# RS-485.net
KiCad netlist of a schematic drawn in Altium Designer
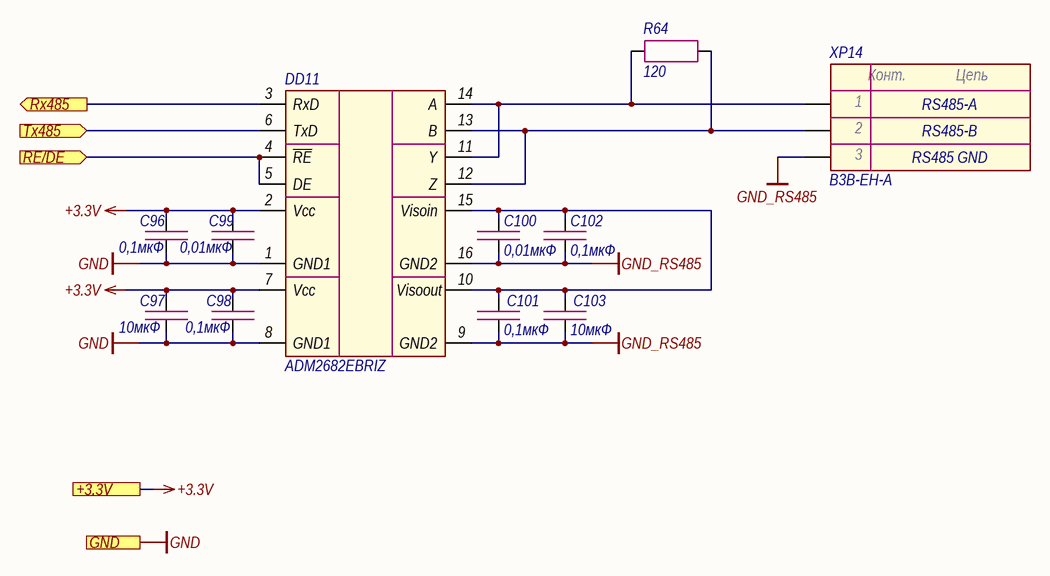
[diagram p0: RS-485.SchDoc]

(export (version "E")
  (design (tool "Eeschema 10.0.6"))
  (components
    (comp (ref "C96")
      (value "0,1мкФ")
      (footprint "Pcb_library:CAP_0603")
      (fields (field (name "MANUFACTURER") "Murata"))
      (libsource (lib "Schem_library") (part "Capacitor"))
    )
    (comp (ref "C97")
      (value "10мкФ")
      (footprint "Pcb_library:CAP_0603")
      (fields (field (name "MANUFACTURER") "Murata"))
      (libsource (lib "Schem_library") (part "Capacitor"))
    )
    (comp (ref "C98")
      (value "0,1мкФ")
      (footprint "Pcb_library:CAP_0603")
      (fields (field (name "MANUFACTURER") "Murata"))
      (libsource (lib "Schem_library") (part "Capacitor"))
    )
    (comp (ref "C99")
      (value "0,01мкФ")
      (footprint "Pcb_library:CAP_0603")
      (fields (field (name "MANUFACTURER") "Murata"))
      (libsource (lib "Schem_library") (part "Capacitor"))
    )
    (comp (ref "C100")
      (value "0,01мкФ")
      (footprint "Pcb_library:CAP_0603")
      (fields (field (name "MANUFACTURER") "Murata"))
      (libsource (lib "Schem_library") (part "Capacitor"))
    )
    (comp (ref "C101")
      (value "0,1мкФ")
      (footprint "Pcb_library:CAP_0603")
      (fields (field (name "MANUFACTURER") "Murata"))
      (libsource (lib "Schem_library") (part "Capacitor"))
    )
    (comp (ref "C102")
      (value "0,1мкФ")
      (footprint "Pcb_library:CAP_0603")
      (fields (field (name "MANUFACTURER") "Murata"))
      (libsource (lib "Schem_library") (part "Capacitor"))
    )
    (comp (ref "C103")
      (value "10мкФ")
      (footprint "Pcb_library:CAP_0603")
      (fields (field (name "MANUFACTURER") "Murata"))
      (libsource (lib "Schem_library") (part "Capacitor"))
    )
    (comp (ref "DD11")
      (value "ADM2682EBRIZ")
      (footprint "Pcb_library:SOIC-16IC")
      (fields (field (name "MANUFACTURER") "Analog Devices"))
      (libsource (lib "Schem_library") (part "ADM2682EBRIZ"))
    )
    (comp (ref "R64")
      (value "120")
      (footprint "Pcb_library:RES_0603")
      (fields (field (name "MANUFACTURER") "Yageo"))
      (libsource (lib "Schem_library") (part "Resistor"))
    )
    (comp (ref "XP14")
      (value "B3B-EH-A")
      (footprint "B3B-EH-A")
      (fields (field (name "MANUFACTURER") "JST"))
      (libsource (lib "Schem_library") (part "Connector-3"))
    )
  )
  (nets
    (net (code "1") (name "+3.3V") (class "Default")
      (node (ref "C96") (pin "1") (pinfunction "1_1") (pintype "passive"))
      (node (ref "C97") (pin "1") (pinfunction "1_1") (pintype "passive"))
      (node (ref "C98") (pin "1") (pinfunction "1_1") (pintype "passive"))
      (node (ref "C99") (pin "2") (pinfunction "2_2") (pintype "passive"))
      (node (ref "DD11") (pin "2") (pinfunction "Vcc_2") (pintype "passive"))
      (node (ref "DD11") (pin "7") (pinfunction "Vcc_7") (pintype "passive"))
    )
    (net (code "2") (name "/RE{slash}DE") (class "Default")
      (node (ref "DD11") (pin "4") (pinfunction "~{RE}_4") (pintype "passive"))
      (node (ref "DD11") (pin "5") (pinfunction "DE_5") (pintype "passive"))
    )
    (net (code "3") (name "/Rx485") (class "Default")
      (node (ref "DD11") (pin "3") (pinfunction "RxD_3") (pintype "passive"))
    )
    (net (code "4") (name "/Tx485") (class "Default")
      (node (ref "DD11") (pin "6") (pinfunction "TxD_6") (pintype "passive"))
    )
    (net (code "5") (name "GND") (class "Default")
      (node (ref "C96") (pin "2") (pinfunction "2_2") (pintype "passive"))
      (node (ref "C97") (pin "2") (pinfunction "2_2") (pintype "passive"))
      (node (ref "C98") (pin "2") (pinfunction "2_2") (pintype "passive"))
      (node (ref "C99") (pin "1") (pinfunction "1_1") (pintype "passive"))
      (node (ref "DD11") (pin "1") (pinfunction "GND1_1") (pintype "passive"))
      (node (ref "DD11") (pin "8") (pinfunction "GND1_8") (pintype "passive"))
    )
    (net (code "6") (name "GND_RS485") (class "Default")
      (node (ref "C100") (pin "1") (pinfunction "1_1") (pintype "passive"))
      (node (ref "C101") (pin "2") (pinfunction "2_2") (pintype "passive"))
      (node (ref "C102") (pin "2") (pinfunction "2_2") (pintype "passive"))
      (node (ref "C103") (pin "2") (pinfunction "2_2") (pintype "passive"))
      (node (ref "DD11") (pin "16") (pinfunction "GND2_16") (pintype "passive"))
      (node (ref "DD11") (pin "9") (pinfunction "GND2_9") (pintype "passive"))
      (node (ref "XP14") (pin "3") (pintype "passive"))
    )
    (net (code "7") (name "Net-(DD11-A)") (class "Default")
      (node (ref "DD11") (pin "11") (pinfunction "Y_11") (pintype "passive"))
      (node (ref "DD11") (pin "14") (pinfunction "A_14") (pintype "passive"))
      (node (ref "R64") (pin "1") (pinfunction "1_1") (pintype "passive"))
      (node (ref "XP14") (pin "1") (pintype "passive"))
    )
    (net (code "8") (name "Net-(DD11-B)") (class "Default")
      (node (ref "DD11") (pin "12") (pinfunction "Z_12") (pintype "passive"))
      (node (ref "DD11") (pin "13") (pinfunction "B_13") (pintype "passive"))
      (node (ref "R64") (pin "2") (pinfunction "2_2") (pintype "passive"))
      (node (ref "XP14") (pin "2") (pintype "passive"))
    )
    (net (code "9") (name "Net-(DD11-Visoin)") (class "Default")
      (node (ref "C100") (pin "2") (pinfunction "2_2") (pintype "passive"))
      (node (ref "C101") (pin "1") (pinfunction "1_1") (pintype "passive"))
      (node (ref "C102") (pin "1") (pinfunction "1_1") (pintype "passive"))
      (node (ref "C103") (pin "1") (pinfunction "1_1") (pintype "passive"))
      (node (ref "DD11") (pin "10") (pinfunction "Visoout_10") (pintype "passive"))
      (node (ref "DD11") (pin "15") (pinfunction "Visoin_15") (pintype "passive"))
    )
  )
)
